# MEMS-preamp.net
KiCad netlist of a schematic drawn in EAGLE
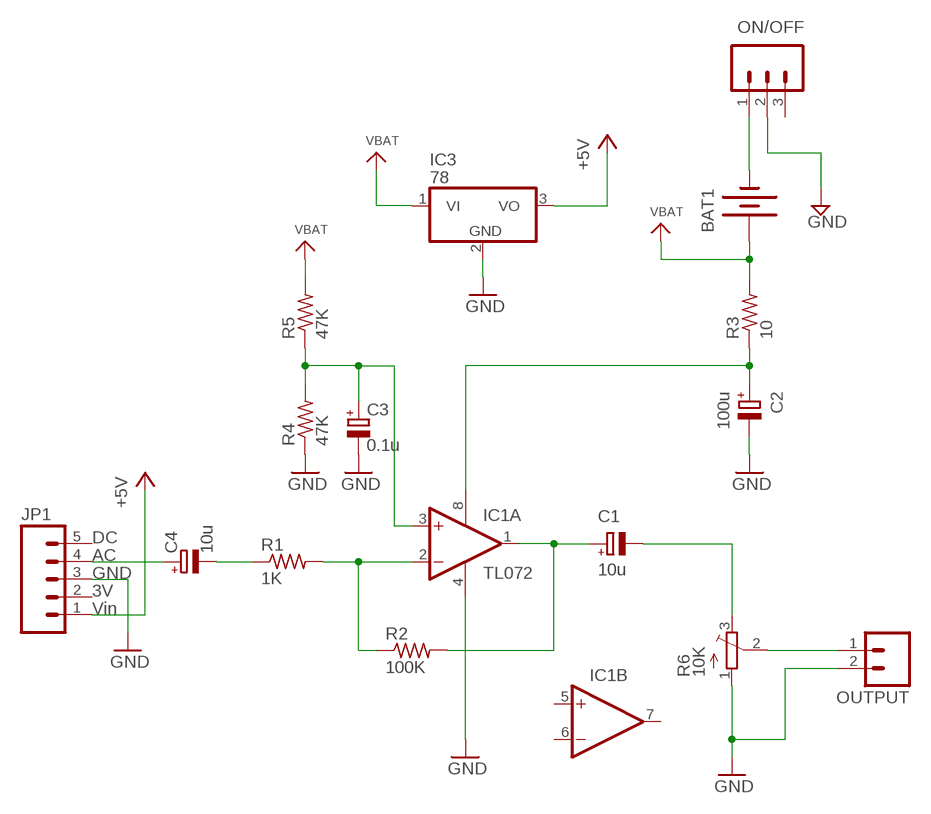
[diagram p0: schematic, sheet 1]

(export (version "E")
  (design (tool "Eeschema 10.0.6"))
  (components
    (comp (ref "BAT1")
      (value "BATTERYA23")
      (footprint "eagle-import:BATTERY-A23")
      (libsource (lib "eagle-import") (part "BATTERYA23"))
    )
    (comp (ref "C1")
      (value "10u")
      (footprint "eagle-import:E2,5-5")
      (libsource (lib "eagle-import") (part "CPOL-EUE2.5-5"))
    )
    (comp (ref "C2")
      (value "100u")
      (footprint "eagle-import:E2,5-5")
      (libsource (lib "eagle-import") (part "CPOL-EUE2.5-5"))
    )
    (comp (ref "C3")
      (value "0.1u")
      (footprint "eagle-import:E2,5-5")
      (libsource (lib "eagle-import") (part "CPOL-EUE2.5-5"))
    )
    (comp (ref "C4")
      (value "10u")
      (footprint "eagle-import:E2,5-5")
      (libsource (lib "eagle-import") (part "CPOL-EUE2.5-5"))
    )
    (comp (ref "IC1")
      (value "OPA2134PA")
      (footprint "eagle-import:DIL08")
      (fields (field (name "IC_NAME") "TL072"))
      (libsource (lib "eagle-import") (part "OPA2PA134"))
    )
    (comp (ref "IC3")
      (value "78")
      (footprint "eagle-import:TO92-")
      (libsource (lib "eagle-import") (part "78"))
    )
    (comp (ref "JP1")
      (value "M05LOCK")
      (footprint "eagle-import:1X05_LOCK")
      (fields
        (field (name "CON1") "Vin")
        (field (name "CON2") "3V")
        (field (name "CON3") "GND")
        (field (name "CON4") "AC")
        (field (name "CON5") "DC")
      )
      (libsource (lib "eagle-import") (part "M05LOCK"))
    )
    (comp (ref "ON/OFF")
      (value "labl")
      (footprint "eagle-import:SPDT-SWITCH")
      (libsource (lib "eagle-import") (part "M03SINGLE-POLE-DOUBLE-THROW"))
    )
    (comp (ref "OUTPUT")
      (value "M02LOCK")
      (footprint "eagle-import:1X02_LOCK")
      (libsource (lib "eagle-import") (part "M02LOCK"))
    )
    (comp (ref "R1")
      (value "1K")
      (footprint "eagle-import:0204_5")
      (libsource (lib "eagle-import") (part "R-US_0204/5"))
    )
    (comp (ref "R2")
      (value "100K")
      (footprint "eagle-import:0204_5")
      (libsource (lib "eagle-import") (part "R-US_0204/5"))
    )
    (comp (ref "R3")
      (value "10")
      (footprint "eagle-import:0204_5")
      (libsource (lib "eagle-import") (part "R-US_0204/5"))
    )
    (comp (ref "R4")
      (value "47K")
      (footprint "eagle-import:0204_5")
      (libsource (lib "eagle-import") (part "R-US_0204/5"))
    )
    (comp (ref "R5")
      (value "47K")
      (footprint "eagle-import:0204_5")
      (libsource (lib "eagle-import") (part "R-US_0204/5"))
    )
    (comp (ref "R6")
      (value "10K")
      (footprint "eagle-import:TRIM-3386")
      (libsource (lib "eagle-import") (part "TRIMPOT3386"))
    )
  )
  (nets
    (net (code "1") (name "+5V") (class "Default")
      (node (ref "IC3") (pin "3") (pinfunction "VO_3") (pintype "passive"))
      (node (ref "JP1") (pin "1") (pinfunction "1_1") (pintype "passive"))
    )
    (net (code "2") (name "GND") (class "Default")
      (node (ref "C2") (pin "-") (pinfunction "-_-") (pintype "passive"))
      (node (ref "C3") (pin "-") (pinfunction "-_-") (pintype "passive"))
      (node (ref "IC1") (pin "4") (pinfunction "V-_4") (pintype "power_in"))
      (node (ref "IC3") (pin "2") (pinfunction "GND_2") (pintype "passive"))
      (node (ref "JP1") (pin "3") (pinfunction "3_3") (pintype "passive"))
      (node (ref "ON/OFF") (pin "2") (pinfunction "2_2") (pintype "passive"))
      (node (ref "OUTPUT") (pin "2") (pinfunction "2_2") (pintype "passive"))
      (node (ref "R4") (pin "1") (pinfunction "1_1") (pintype "passive"))
      (node (ref "R6") (pin "1") (pinfunction "A_1") (pintype "passive"))
    )
    (net (code "3") (name "Net-(BAT1--)") (class "Default")
      (node (ref "BAT1") (pin "GND@1") (pinfunction "-_GND@1") (pintype "power_in"))
      (node (ref "ON/OFF") (pin "1") (pinfunction "1_1") (pintype "passive"))
    )
    (net (code "4") (name "Net-(C4-Pad+)") (class "Default")
      (node (ref "C4") (pin "+") (pinfunction "+_+") (pintype "passive"))
      (node (ref "JP1") (pin "4") (pinfunction "4_4") (pintype "passive"))
    )
    (net (code "5") (name "Net-(C4-Pad-)") (class "Default")
      (node (ref "C4") (pin "-") (pinfunction "-_-") (pintype "passive"))
      (node (ref "R1") (pin "1") (pinfunction "1_1") (pintype "passive"))
    )
    (net (code "6") (name "Net-(IC1A-+IN)") (class "Default")
      (node (ref "C3") (pin "+") (pinfunction "+_+") (pintype "passive"))
      (node (ref "IC1") (pin "3") (pinfunction "+IN_3") (pintype "input"))
      (node (ref "R4") (pin "2") (pinfunction "2_2") (pintype "passive"))
      (node (ref "R5") (pin "1") (pinfunction "1_1") (pintype "passive"))
    )
    (net (code "7") (name "Net-(IC1A--IN)") (class "Default")
      (node (ref "IC1") (pin "2") (pinfunction "-IN_2") (pintype "input"))
      (node (ref "R1") (pin "2") (pinfunction "2_2") (pintype "passive"))
      (node (ref "R2") (pin "1") (pinfunction "1_1") (pintype "passive"))
    )
    (net (code "8") (name "Net-(IC1A-OUT)") (class "Default")
      (node (ref "C1") (pin "+") (pinfunction "+_+") (pintype "passive"))
      (node (ref "IC1") (pin "1") (pinfunction "OUT_1") (pintype "output"))
      (node (ref "R2") (pin "2") (pinfunction "2_2") (pintype "passive"))
    )
    (net (code "9") (name "Net-(IC1A-V+)") (class "Default")
      (node (ref "C2") (pin "+") (pinfunction "+_+") (pintype "passive"))
      (node (ref "IC1") (pin "8") (pinfunction "V+_8") (pintype "power_in"))
      (node (ref "R3") (pin "1") (pinfunction "1_1") (pintype "passive"))
    )
    (net (code "10") (name "Net-(R6-E)") (class "Default")
      (node (ref "C1") (pin "-") (pinfunction "-_-") (pintype "passive"))
      (node (ref "R6") (pin "3") (pinfunction "E_3") (pintype "passive"))
    )
    (net (code "11") (name "Net-(R6-S)") (class "Default")
      (node (ref "OUTPUT") (pin "1") (pinfunction "1_1") (pintype "passive"))
      (node (ref "R6") (pin "2") (pinfunction "S_2") (pintype "passive"))
    )
    (net (code "12") (name "VBAT") (class "Default")
      (node (ref "BAT1") (pin "PWR@1") (pinfunction "+_PWR@1") (pintype "power_in"))
      (node (ref "IC3") (pin "1") (pinfunction "VI_1") (pintype "input"))
      (node (ref "R3") (pin "2") (pinfunction "2_2") (pintype "passive"))
      (node (ref "R5") (pin "2") (pinfunction "2_2") (pintype "passive"))
    )
    (net (code "13") (name "unconnected-(IC1B-+IN-Pad5)") (class "Default")
      (node (ref "IC1") (pin "5") (pinfunction "+IN_5") (pintype "input"))
    )
    (net (code "14") (name "unconnected-(IC1B--IN-Pad6)") (class "Default")
      (node (ref "IC1") (pin "6") (pinfunction "-IN_6") (pintype "input"))
    )
    (net (code "15") (name "unconnected-(IC1B-OUT-Pad7)") (class "Default")
      (node (ref "IC1") (pin "7") (pinfunction "OUT_7") (pintype "output"))
    )
    (net (code "16") (name "unconnected-(JP1-Pad2)") (class "Default")
      (node (ref "JP1") (pin "2") (pinfunction "2_2") (pintype "passive"))
    )
    (net (code "17") (name "unconnected-(JP1-Pad5)") (class "Default")
      (node (ref "JP1") (pin "5") (pinfunction "5_5") (pintype "passive"))
    )
    (net (code "18") (name "unconnected-(ON/OFF-Pad3)") (class "Default")
      (node (ref "ON/OFF") (pin "3") (pinfunction "3_3") (pintype "passive"))
    )
  )
)
